# Amp_Relay.net
KiCad netlist of a schematic drawn in EAGLE
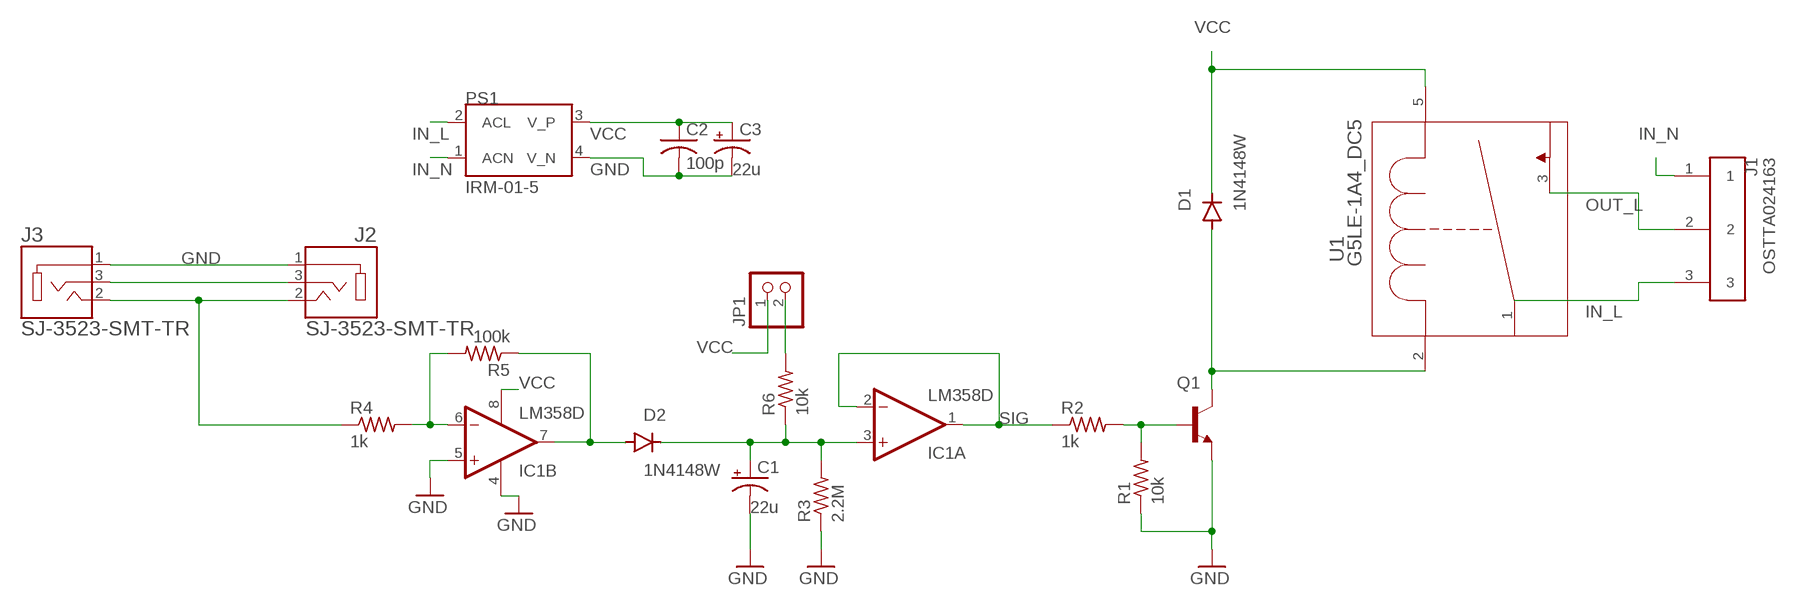
[diagram p0: schematic, sheet 1]

(export (version "E")
  (design (tool "Eeschema 10.0.6"))
  (components
    (comp (ref "C1")
      (value "WE-CAP")
      (footprint "eagle-import:WE-CAP")
      (fields (field (name "C") "22u"))
      (libsource (lib "eagle-import") (part "WE-CAP"))
    )
    (comp (ref "C2")
      (value "100p")
      (footprint "eagle-import:C0805")
      (libsource (lib "eagle-import") (part "C-USC0805"))
    )
    (comp (ref "C3")
      (value "WE-CAP")
      (footprint "eagle-import:WE-CAP")
      (fields (field (name "C") "22u"))
      (libsource (lib "eagle-import") (part "WE-CAP"))
    )
    (comp (ref "D1")
      (value "1N4148W")
      (footprint "eagle-import:SOD123")
      (libsource (lib "eagle-import") (part "DIODE-SOD123"))
    )
    (comp (ref "D2")
      (value "1N4148W")
      (footprint "eagle-import:SOD123")
      (libsource (lib "eagle-import") (part "DIODE-SOD123"))
    )
    (comp (ref "IC1")
      (value "LM358D")
      (footprint "eagle-import:SO08")
      (libsource (lib "eagle-import") (part "LM358D"))
    )
    (comp (ref "J1")
      (value "OSTTA024163")
      (footprint "eagle-import:OSTTA024163")
      (libsource (lib "eagle-import") (part "OSTTA024163"))
    )
    (comp (ref "J2")
      (value "SJ-3523-SMT-TR")
      (footprint "eagle-import:CUI_SJ-3523-SMT-TR")
      (fields (field (name "DIGI-KEY_PART_NUMBER") "CP-3523SJCT-ND") (field (name "MF") "CUI Inc."))
      (libsource (lib "eagle-import") (part "SJ-3523-SMT-TR"))
    )
    (comp (ref "J3")
      (value "SJ-3523-SMT-TR")
      (footprint "eagle-import:CUI_SJ-3523-SMT-TR")
      (fields (field (name "DIGI-KEY_PART_NUMBER") "CP-3523SJCT-ND") (field (name "MF") "CUI Inc."))
      (libsource (lib "eagle-import") (part "SJ-3523-SMT-TR"))
    )
    (comp (ref "JP1")
      (value "PINHD-1X2")
      (footprint "eagle-import:1X02")
      (libsource (lib "eagle-import") (part "PINHD-1X2"))
    )
    (comp (ref "PS1")
      (value "IRM-01-5")
      (footprint "eagle-import:CONV_IRM-01-5")
      (fields (field (name "DIGI-KEY_PART_NUMBER") "1866-2998-ND") (field (name "MF") "MEAN WELL"))
      (libsource (lib "eagle-import") (part "IRM-01-5"))
    )
    (comp (ref "Q1")
      (value "BC849SMD")
      (footprint "eagle-import:SOT23-BEC")
      (libsource (lib "eagle-import") (part "BC849SMD"))
    )
    (comp (ref "R1")
      (value "10k")
      (footprint "eagle-import:R1206")
      (libsource (lib "eagle-import") (part "R-US_R1206"))
    )
    (comp (ref "R2")
      (value "1k")
      (footprint "eagle-import:R0805")
      (libsource (lib "eagle-import") (part "R-US_R0805"))
    )
    (comp (ref "R3")
      (value "2.2M")
      (footprint "eagle-import:R1206")
      (libsource (lib "eagle-import") (part "R-US_R1206"))
    )
    (comp (ref "R4")
      (value "1k")
      (footprint "eagle-import:R0805")
      (libsource (lib "eagle-import") (part "R-US_R0805"))
    )
    (comp (ref "R5")
      (value "100k")
      (footprint "eagle-import:R1206")
      (libsource (lib "eagle-import") (part "R-US_R1206"))
    )
    (comp (ref "R6")
      (value "10k")
      (footprint "eagle-import:R1206")
      (libsource (lib "eagle-import") (part "R-US_R1206"))
    )
    (comp (ref "U1")
      (value "G5LE-1A4_DC5")
      (footprint "eagle-import:RELAY_G5LE-1A")
      (fields (field (name "MANUFACTURER_PART_NUMBER") "G5LE1A4 DC5"))
      (libsource (lib "eagle-import") (part "G5LE-1A4_DC5"))
    )
  )
  (nets
    (net (code "1") (name "/IN_L") (class "Default")
      (node (ref "J1") (pin "3") (pinfunction "3_3") (pintype "bidirectional"))
      (node (ref "PS1") (pin "2") (pinfunction "ACL_2") (pintype "input"))
      (node (ref "U1") (pin "1") (pinfunction "2_1") (pintype "passive"))
    )
    (net (code "2") (name "/IN_N") (class "Default")
      (node (ref "J1") (pin "1") (pinfunction "1_1") (pintype "bidirectional"))
      (node (ref "PS1") (pin "1") (pinfunction "ACN_1") (pintype "input"))
    )
    (net (code "3") (name "/OUT_L") (class "Default")
      (node (ref "J1") (pin "2") (pinfunction "2_2") (pintype "bidirectional"))
      (node (ref "U1") (pin "3") (pinfunction "3_3") (pintype "passive"))
    )
    (net (code "4") (name "/SIG") (class "Default")
      (node (ref "IC1") (pin "1") (pinfunction "OUT_1") (pintype "output"))
      (node (ref "IC1") (pin "2") (pinfunction "-IN_2") (pintype "input"))
      (node (ref "R2") (pin "1") (pinfunction "1_1") (pintype "passive"))
    )
    (net (code "5") (name "/VCC") (class "Default")
      (node (ref "C2") (pin "1") (pinfunction "1_1") (pintype "passive"))
      (node (ref "C3") (pin "+") (pinfunction "+_+") (pintype "passive"))
      (node (ref "D1") (pin "C") (pinfunction "C_C") (pintype "passive"))
      (node (ref "IC1") (pin "8") (pinfunction "V+_8") (pintype "power_in"))
      (node (ref "JP1") (pin "1") (pinfunction "1_1") (pintype "passive"))
      (node (ref "PS1") (pin "3") (pinfunction "V_P_3") (pintype "output"))
      (node (ref "U1") (pin "5") (pinfunction "4_5") (pintype "passive"))
    )
    (net (code "6") (name "GND") (class "Default")
      (node (ref "C1") (pin "-") (pinfunction "-_-") (pintype "passive"))
      (node (ref "C2") (pin "2") (pinfunction "2_2") (pintype "passive"))
      (node (ref "C3") (pin "-") (pinfunction "-_-") (pintype "passive"))
      (node (ref "IC1") (pin "4") (pinfunction "V-_4") (pintype "power_in"))
      (node (ref "IC1") (pin "5") (pinfunction "+IN_5") (pintype "input"))
      (node (ref "J2") (pin "1") (pinfunction "1_1") (pintype "passive"))
      (node (ref "J3") (pin "1") (pinfunction "1_1") (pintype "passive"))
      (node (ref "PS1") (pin "4") (pinfunction "V_N_4") (pintype "output"))
      (node (ref "Q1") (pin "E") (pinfunction "E_E") (pintype "passive"))
      (node (ref "R1") (pin "1") (pinfunction "1_1") (pintype "passive"))
      (node (ref "R3") (pin "1") (pinfunction "1_1") (pintype "passive"))
    )
    (net (code "7") (name "Net-(IC1A-+IN)") (class "Default")
      (node (ref "C1") (pin "+") (pinfunction "+_+") (pintype "passive"))
      (node (ref "D2") (pin "C") (pinfunction "C_C") (pintype "passive"))
      (node (ref "IC1") (pin "3") (pinfunction "+IN_3") (pintype "input"))
      (node (ref "R3") (pin "2") (pinfunction "2_2") (pintype "passive"))
      (node (ref "R6") (pin "1") (pinfunction "1_1") (pintype "passive"))
    )
    (net (code "8") (name "Net-(IC1B--IN)") (class "Default")
      (node (ref "IC1") (pin "6") (pinfunction "-IN_6") (pintype "input"))
      (node (ref "R4") (pin "2") (pinfunction "2_2") (pintype "passive"))
      (node (ref "R5") (pin "2") (pinfunction "2_2") (pintype "passive"))
    )
    (net (code "9") (name "Net-(IC1B-OUT)") (class "Default")
      (node (ref "D2") (pin "A") (pinfunction "A_A") (pintype "passive"))
      (node (ref "IC1") (pin "7") (pinfunction "OUT_7") (pintype "output"))
      (node (ref "R5") (pin "1") (pinfunction "1_1") (pintype "passive"))
    )
    (net (code "10") (name "Net-(J2-Pad2)") (class "Default")
      (node (ref "J2") (pin "2") (pinfunction "2_2") (pintype "passive"))
      (node (ref "J3") (pin "2") (pinfunction "2_2") (pintype "passive"))
      (node (ref "R4") (pin "1") (pinfunction "1_1") (pintype "passive"))
    )
    (net (code "11") (name "Net-(J2-Pad3)") (class "Default")
      (node (ref "J2") (pin "3") (pinfunction "3_3") (pintype "passive"))
      (node (ref "J3") (pin "3") (pinfunction "3_3") (pintype "passive"))
    )
    (net (code "12") (name "Net-(JP1-Pad2)") (class "Default")
      (node (ref "JP1") (pin "2") (pinfunction "2_2") (pintype "passive"))
      (node (ref "R6") (pin "2") (pinfunction "2_2") (pintype "passive"))
    )
    (net (code "13") (name "Net-(Q1-PadB)") (class "Default")
      (node (ref "Q1") (pin "B") (pinfunction "B_B") (pintype "passive"))
      (node (ref "R1") (pin "2") (pinfunction "2_2") (pintype "passive"))
      (node (ref "R2") (pin "2") (pinfunction "2_2") (pintype "passive"))
    )
    (net (code "14") (name "Net-(U1-1)") (class "Default")
      (node (ref "D1") (pin "A") (pinfunction "A_A") (pintype "passive"))
      (node (ref "Q1") (pin "C") (pinfunction "C_C") (pintype "passive"))
      (node (ref "U1") (pin "2") (pinfunction "1_2") (pintype "passive"))
    )
  )
)
